# divchrono-encoder.net
KiCad netlist of a schematic drawn in EAGLE
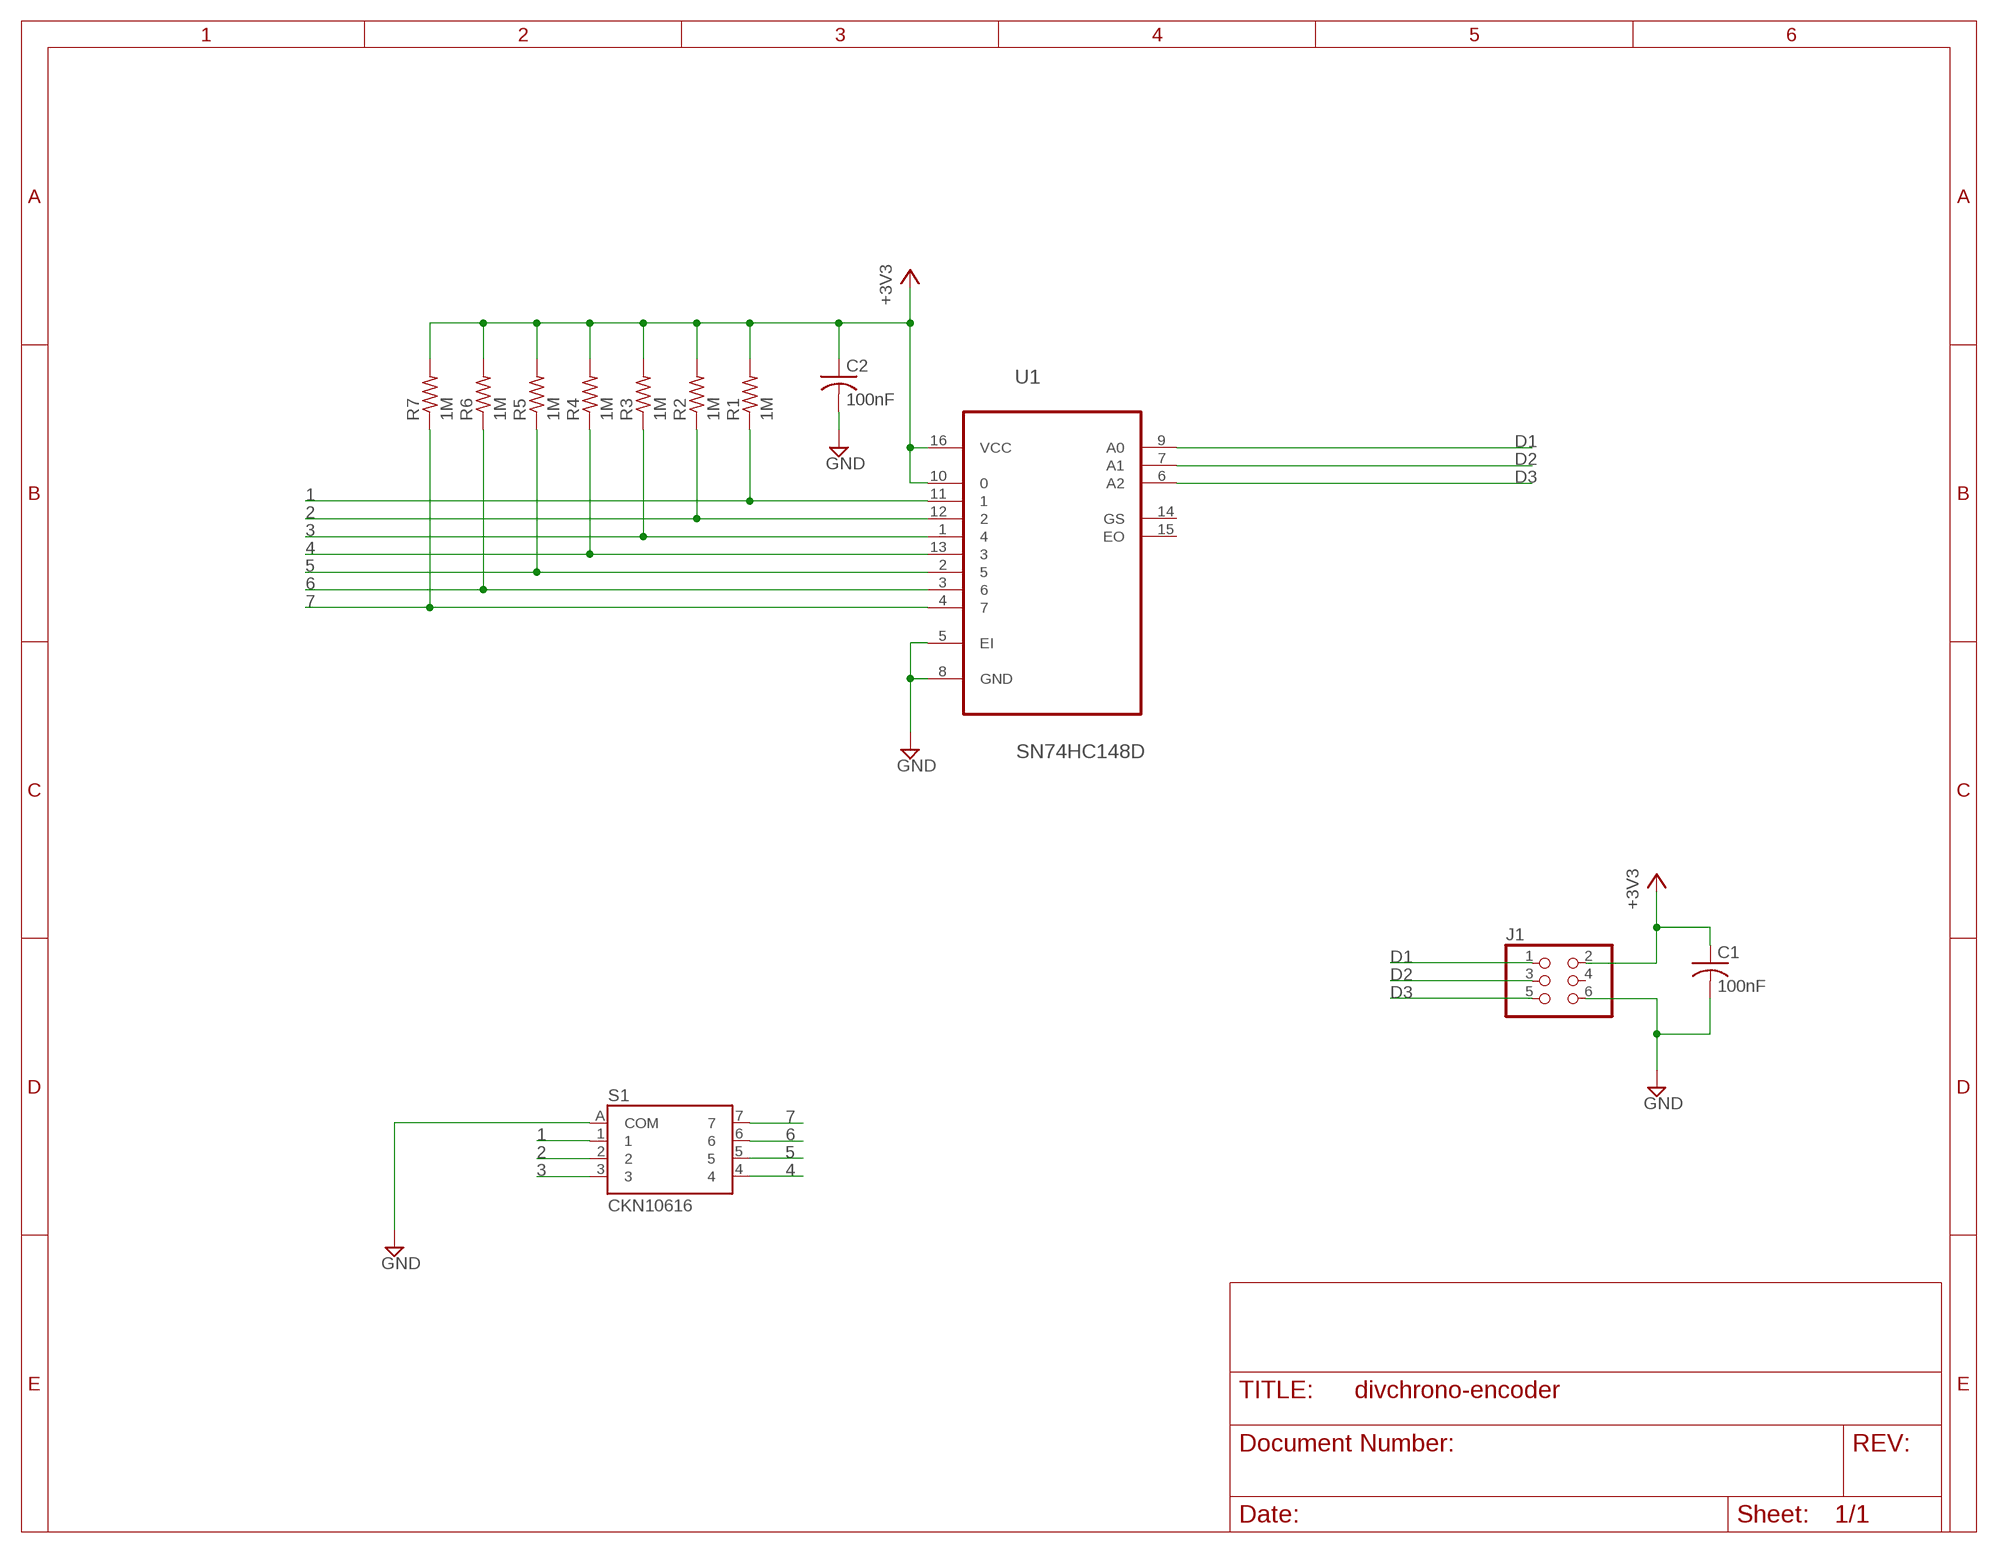
[diagram p0: schematic, sheet 1]

(export (version "E")
  (design (tool "Eeschema 10.0.6"))
  (components
    (comp (ref "C1")
      (value "100nF")
      (footprint "eagle-import:C1206")
      (libsource (lib "eagle-import") (part "C-USC1206"))
    )
    (comp (ref "C2")
      (value "100nF")
      (footprint "eagle-import:C1206")
      (libsource (lib "eagle-import") (part "C-USC1206"))
    )
    (comp (ref "J1")
      (value "PINHD-2X3")
      (footprint "eagle-import:2X03")
      (libsource (lib "eagle-import") (part "PINHD-2X3"))
    )
    (comp (ref "R1")
      (value "1M")
      (footprint "eagle-import:R1206")
      (libsource (lib "eagle-import") (part "R-US_R1206"))
    )
    (comp (ref "R2")
      (value "1M")
      (footprint "eagle-import:R1206")
      (libsource (lib "eagle-import") (part "R-US_R1206"))
    )
    (comp (ref "R3")
      (value "1M")
      (footprint "eagle-import:R1206")
      (libsource (lib "eagle-import") (part "R-US_R1206"))
    )
    (comp (ref "R4")
      (value "1M")
      (footprint "eagle-import:R1206")
      (libsource (lib "eagle-import") (part "R-US_R1206"))
    )
    (comp (ref "R5")
      (value "1M")
      (footprint "eagle-import:R1206")
      (libsource (lib "eagle-import") (part "R-US_R1206"))
    )
    (comp (ref "R6")
      (value "1M")
      (footprint "eagle-import:R1206")
      (libsource (lib "eagle-import") (part "R-US_R1206"))
    )
    (comp (ref "R7")
      (value "1M")
      (footprint "eagle-import:R1206")
      (libsource (lib "eagle-import") (part "R-US_R1206"))
    )
    (comp (ref "S1")
      (value "CKN10616")
      (footprint "eagle-import:CKN10616")
      (libsource (lib "eagle-import") (part "CKN10616"))
    )
    (comp (ref "U1")
      (value "SN74HC148D")
      (footprint "eagle-import:SOIC127P600X175-16N")
      (libsource (lib "eagle-import") (part "SN74HC148D"))
    )
  )
  (nets
    (net (code "1") (name "+3V3") (class "Default")
      (node (ref "C1") (pin "1") (pinfunction "1_1") (pintype "passive"))
      (node (ref "C2") (pin "1") (pinfunction "1_1") (pintype "passive"))
      (node (ref "J1") (pin "2") (pinfunction "2_2") (pintype "passive"))
      (node (ref "R1") (pin "2") (pinfunction "2_2") (pintype "passive"))
      (node (ref "R2") (pin "2") (pinfunction "2_2") (pintype "passive"))
      (node (ref "R3") (pin "2") (pinfunction "2_2") (pintype "passive"))
      (node (ref "R4") (pin "2") (pinfunction "2_2") (pintype "passive"))
      (node (ref "R5") (pin "2") (pinfunction "2_2") (pintype "passive"))
      (node (ref "R6") (pin "2") (pinfunction "2_2") (pintype "passive"))
      (node (ref "R7") (pin "2") (pinfunction "2_2") (pintype "passive"))
      (node (ref "U1") (pin "10") (pinfunction "0_10") (pintype "input"))
      (node (ref "U1") (pin "16") (pinfunction "VCC_16") (pintype "power_in"))
    )
    (net (code "2") (name "/1") (class "Default")
      (node (ref "R1") (pin "1") (pinfunction "1_1") (pintype "passive"))
      (node (ref "S1") (pin "1") (pinfunction "1_1") (pintype "bidirectional"))
      (node (ref "U1") (pin "11") (pinfunction "1_11") (pintype "input"))
    )
    (net (code "3") (name "/2") (class "Default")
      (node (ref "R2") (pin "1") (pinfunction "1_1") (pintype "passive"))
      (node (ref "S1") (pin "2") (pinfunction "2_2") (pintype "bidirectional"))
      (node (ref "U1") (pin "12") (pinfunction "2_12") (pintype "input"))
    )
    (net (code "4") (name "/3") (class "Default")
      (node (ref "R3") (pin "1") (pinfunction "1_1") (pintype "passive"))
      (node (ref "S1") (pin "3") (pinfunction "3_3") (pintype "bidirectional"))
      (node (ref "U1") (pin "1") (pinfunction "4_1") (pintype "input"))
    )
    (net (code "5") (name "/4") (class "Default")
      (node (ref "R4") (pin "1") (pinfunction "1_1") (pintype "passive"))
      (node (ref "S1") (pin "4") (pinfunction "4_4") (pintype "bidirectional"))
      (node (ref "U1") (pin "13") (pinfunction "3_13") (pintype "input"))
    )
    (net (code "6") (name "/5") (class "Default")
      (node (ref "R5") (pin "1") (pinfunction "1_1") (pintype "passive"))
      (node (ref "S1") (pin "5") (pinfunction "5_5") (pintype "bidirectional"))
      (node (ref "U1") (pin "2") (pinfunction "5_2") (pintype "input"))
    )
    (net (code "7") (name "/6") (class "Default")
      (node (ref "R6") (pin "1") (pinfunction "1_1") (pintype "passive"))
      (node (ref "S1") (pin "6") (pinfunction "6_6") (pintype "bidirectional"))
      (node (ref "U1") (pin "3") (pinfunction "6_3") (pintype "input"))
    )
    (net (code "8") (name "/7") (class "Default")
      (node (ref "R7") (pin "1") (pinfunction "1_1") (pintype "passive"))
      (node (ref "S1") (pin "7") (pinfunction "7_7") (pintype "bidirectional"))
      (node (ref "U1") (pin "4") (pinfunction "7_4") (pintype "input"))
    )
    (net (code "9") (name "/D1") (class "Default")
      (node (ref "J1") (pin "1") (pinfunction "1_1") (pintype "passive"))
      (node (ref "U1") (pin "9") (pinfunction "A0_9") (pintype "output"))
    )
    (net (code "10") (name "/D2") (class "Default")
      (node (ref "J1") (pin "3") (pinfunction "3_3") (pintype "passive"))
      (node (ref "U1") (pin "7") (pinfunction "A1_7") (pintype "output"))
    )
    (net (code "11") (name "/D3") (class "Default")
      (node (ref "J1") (pin "5") (pinfunction "5_5") (pintype "passive"))
      (node (ref "U1") (pin "6") (pinfunction "A2_6") (pintype "output"))
    )
    (net (code "12") (name "GND") (class "Default")
      (node (ref "C1") (pin "2") (pinfunction "2_2") (pintype "passive"))
      (node (ref "C2") (pin "2") (pinfunction "2_2") (pintype "passive"))
      (node (ref "J1") (pin "6") (pinfunction "6_6") (pintype "passive"))
      (node (ref "S1") (pin "A") (pinfunction "COM_A") (pintype "bidirectional"))
      (node (ref "U1") (pin "5") (pinfunction "EI_5") (pintype "input"))
      (node (ref "U1") (pin "8") (pinfunction "GND_8") (pintype "passive"))
    )
    (net (code "13") (name "unconnected-(J1-Pad4)") (class "Default")
      (node (ref "J1") (pin "4") (pinfunction "4_4") (pintype "passive"))
    )
    (net (code "14") (name "unconnected-(U1-EO-Pad15)") (class "Default")
      (node (ref "U1") (pin "15") (pinfunction "EO_15") (pintype "output"))
    )
    (net (code "15") (name "unconnected-(U1-GS-Pad14)") (class "Default")
      (node (ref "U1") (pin "14") (pinfunction "GS_14") (pintype "output"))
    )
  )
)
